# Main.net
KiCad netlist of a schematic drawn in Altium Designer
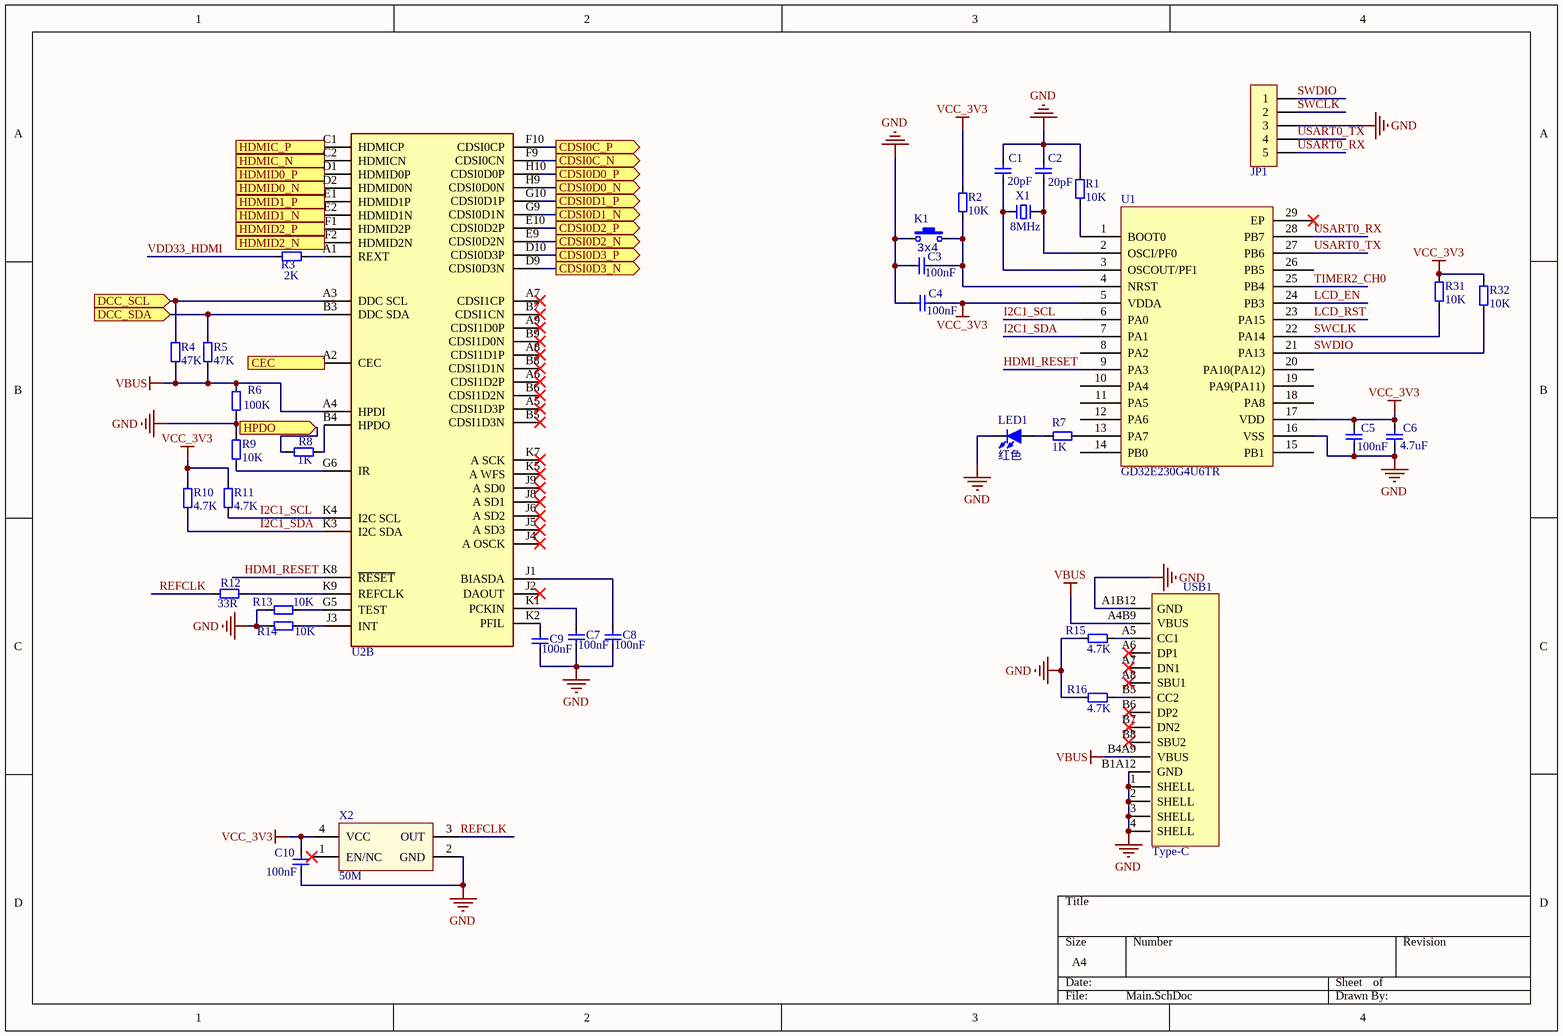
[diagram p0: Main.SchDoc]

(export (version "E")
  (design (tool "Eeschema 10.0.6"))
  (components
    (comp (ref "C1")
      (value "20pF")
      (footprint "C0402_L")
      (description "贴片电容")
      (libsource (lib "0.1 - 电阻-电容-电感-磁珠-电位器") (part "C"))
    )
    (comp (ref "C2")
      (value "20pF")
      (footprint "C0402_L")
      (description "贴片电容")
      (libsource (lib "0.1 - 电阻-电容-电感-磁珠-电位器") (part "C"))
    )
    (comp (ref "C3")
      (value "100nF")
      (footprint "C0402_L")
      (description "贴片电容")
      (libsource (lib "0.1 - 电阻-电容-电感-磁珠-电位器") (part "C"))
    )
    (comp (ref "C4")
      (value "100nF")
      (footprint "C0402_L")
      (description "贴片电容")
      (libsource (lib "0.1 - 电阻-电容-电感-磁珠-电位器") (part "C"))
    )
    (comp (ref "C5")
      (value "100nF")
      (footprint "C0402_L")
      (description "贴片电容")
      (libsource (lib "0.1 - 电阻-电容-电感-磁珠-电位器") (part "C"))
    )
    (comp (ref "C6")
      (value "4.7uF")
      (footprint "C0402_L")
      (description "贴片电容")
      (libsource (lib "0.1 - 电阻-电容-电感-磁珠-电位器") (part "C"))
    )
    (comp (ref "C7")
      (value "100nF")
      (footprint "C0402_L")
      (description "贴片电容")
      (libsource (lib "0.1 - 电阻-电容-电感-磁珠-电位器") (part "C"))
    )
    (comp (ref "C8")
      (value "100nF")
      (footprint "C0402_L")
      (description "贴片电容")
      (libsource (lib "0.1 - 电阻-电容-电感-磁珠-电位器") (part "C"))
    )
    (comp (ref "C9")
      (value "100nF")
      (footprint "C0402_L")
      (description "贴片电容")
      (libsource (lib "0.1 - 电阻-电容-电感-磁珠-电位器") (part "C"))
    )
    (comp (ref "C10")
      (value "100nF")
      (footprint "C0402_L")
      (description "贴片电容")
      (libsource (lib "0.1 - 电阻-电容-电感-磁珠-电位器") (part "C"))
    )
    (comp (ref "JP1")
      (value "HDR-1X5")
      (footprint "Test-2.54-5P")
      (description "5P接插件")
      (fields (field (name "版权归属") "源创客"))
      (libsource (lib "4.5   - 接插件-脚距2.54") (part "Header 5"))
    )
    (comp (ref "K1")
      (value "3x4")
      (footprint "ButtonTACT_3x4x2_180H")
      (description "Button")
      (libsource (lib "User") (part "ButtonTACT_3x4x2_180"))
    )
    (comp (ref "LED1")
      (value "红色")
      (footprint "LED0402")
      (description "贴片LED")
      (libsource (lib "0.3 - LED发光二极管") (part "LED-SMD"))
    )
    (comp (ref "R1")
      (value "10K")
      (footprint "R0402_L")
      (description "贴片电阻")
      (libsource (lib "0.1 - 电阻-电容-电感-磁珠-电位器") (part "R"))
    )
    (comp (ref "R2")
      (value "10K")
      (footprint "R0402_L")
      (description "贴片电阻")
      (libsource (lib "0.1 - 电阻-电容-电感-磁珠-电位器") (part "R"))
    )
    (comp (ref "R3")
      (value "2K")
      (footprint "R0402_L")
      (description "贴片电阻")
      (libsource (lib "0.1 - 电阻-电容-电感-磁珠-电位器") (part "R"))
    )
    (comp (ref "R4")
      (value "47K")
      (footprint "R0402_L")
      (description "贴片电阻")
      (libsource (lib "0.1 - 电阻-电容-电感-磁珠-电位器") (part "R"))
    )
    (comp (ref "R5")
      (value "47K")
      (footprint "R0402_L")
      (description "贴片电阻")
      (libsource (lib "0.1 - 电阻-电容-电感-磁珠-电位器") (part "R"))
    )
    (comp (ref "R6")
      (value "100K")
      (footprint "R0402_L")
      (description "贴片电阻")
      (libsource (lib "0.1 - 电阻-电容-电感-磁珠-电位器") (part "R"))
    )
    (comp (ref "R7")
      (value "1K")
      (footprint "R0402_L")
      (description "贴片电阻")
      (libsource (lib "0.1 - 电阻-电容-电感-磁珠-电位器") (part "R"))
    )
    (comp (ref "R8")
      (value "1K")
      (footprint "R0402_L")
      (description "贴片电阻")
      (libsource (lib "0.1 - 电阻-电容-电感-磁珠-电位器") (part "R"))
    )
    (comp (ref "R9")
      (value "10K")
      (footprint "R0402_L")
      (description "贴片电阻")
      (libsource (lib "0.1 - 电阻-电容-电感-磁珠-电位器") (part "R"))
    )
    (comp (ref "R10")
      (value "4.7K")
      (footprint "R0402_L")
      (description "贴片电阻")
      (libsource (lib "0.1 - 电阻-电容-电感-磁珠-电位器") (part "R"))
    )
    (comp (ref "R11")
      (value "4.7K")
      (footprint "R0402_L")
      (description "贴片电阻")
      (libsource (lib "0.1 - 电阻-电容-电感-磁珠-电位器") (part "R"))
    )
    (comp (ref "R12")
      (value "33R")
      (footprint "R0402_L")
      (description "贴片电阻")
      (libsource (lib "0.1 - 电阻-电容-电感-磁珠-电位器") (part "R"))
    )
    (comp (ref "R13")
      (value "10K")
      (footprint "R0402_L")
      (description "贴片电阻")
      (libsource (lib "0.1 - 电阻-电容-电感-磁珠-电位器") (part "R"))
    )
    (comp (ref "R14")
      (value "10K")
      (footprint "R0402_L")
      (description "贴片电阻")
      (libsource (lib "0.1 - 电阻-电容-电感-磁珠-电位器") (part "R"))
    )
    (comp (ref "R15")
      (value "4.7K")
      (footprint "R0402_L")
      (description "贴片电阻")
      (libsource (lib "0.1 - 电阻-电容-电感-磁珠-电位器") (part "R"))
    )
    (comp (ref "R16")
      (value "4.7K")
      (footprint "R0402_L")
      (description "贴片电阻")
      (libsource (lib "0.1 - 电阻-电容-电感-磁珠-电位器") (part "R"))
    )
    (comp (ref "R31")
      (value "10K")
      (footprint "R0402_L")
      (description "贴片电阻")
      (libsource (lib "0.1 - 电阻-电容-电感-磁珠-电位器") (part "R"))
    )
    (comp (ref "R32")
      (value "10K")
      (footprint "R0402_L")
      (description "贴片电阻")
      (libsource (lib "0.1 - 电阻-电容-电感-磁珠-电位器") (part "R"))
    )
    (comp (ref "U1")
      (value "GD32E230G4U6TR")
      (footprint "GD32E230G4U6TR")
      (libsource (lib "User") (part "GD32E230G4U6TR"))
    )
    (comp (ref "U2")
      (value "TC358870XBG")
      (footprint "TC358870XBG")
      (libsource (lib "User") (part "TC358870XBG"))
    )
    (comp (ref "USB1") (value "Type-C") (footprint "Type-C 16P") (libsource (lib "User") (part "Type-C")))
    (comp (ref "X1")
      (value "8MHz")
      (footprint "OSC 5032-8M")
      (description "2脚无源脚晶振")
      (libsource (lib "0.5 - 保险丝-晶振-光耦") (part "XTAL-2P"))
    )
    (comp (ref "X2")
      (value "50M")
      (footprint "OSC 3225-4P")
      (description "4脚有源晶振")
      (libsource (lib "0.5 - 保险丝-晶振-光耦") (part "XTAL-ACT-4P"))
    )
  )
  (nets
    (net (code "1") (name "/CDSI0C_N") (class "Default")
      (node (ref "U2") (pin "F9") (pinfunction "CDSI0CN_F9") (pintype "passive"))
    )
    (net (code "2") (name "/CDSI0C_P") (class "Default")
      (node (ref "U2") (pin "F10") (pinfunction "CDSI0CP_F10") (pintype "passive"))
    )
    (net (code "3") (name "/CDSI0D0_N") (class "Default")
      (node (ref "U2") (pin "H9") (pinfunction "CDSI0D0N_H9") (pintype "passive"))
    )
    (net (code "4") (name "/CDSI0D0_P") (class "Default")
      (node (ref "U2") (pin "H10") (pinfunction "CDSI0D0P_H10") (pintype "passive"))
    )
    (net (code "5") (name "/CDSI0D1_N") (class "Default")
      (node (ref "U2") (pin "G9") (pinfunction "CDSI0D1N_G9") (pintype "passive"))
    )
    (net (code "6") (name "/CDSI0D1_P") (class "Default")
      (node (ref "U2") (pin "G10") (pinfunction "CDSI0D1P_G10") (pintype "passive"))
    )
    (net (code "7") (name "/CDSI0D2_N") (class "Default")
      (node (ref "U2") (pin "E9") (pinfunction "CDSI0D2N_E9") (pintype "passive"))
    )
    (net (code "8") (name "/CDSI0D2_P") (class "Default")
      (node (ref "U2") (pin "E10") (pinfunction "CDSI0D2P_E10") (pintype "passive"))
    )
    (net (code "9") (name "/CDSI0D3_N") (class "Default")
      (node (ref "U2") (pin "D9") (pinfunction "CDSI0D3N_D9") (pintype "passive"))
    )
    (net (code "10") (name "/CDSI0D3_P") (class "Default")
      (node (ref "U2") (pin "D10") (pinfunction "CDSI0D3P_D10") (pintype "passive"))
    )
    (net (code "11") (name "/CEC") (class "Default")
      (node (ref "U2") (pin "A2") (pinfunction "CEC_A2") (pintype "passive"))
    )
    (net (code "12") (name "/DCC_SCL") (class "Default")
      (node (ref "R4") (pin "2") (pinfunction "2_2") (pintype "passive"))
      (node (ref "U2") (pin "A3") (pinfunction "DDC_SCL_A3") (pintype "passive"))
    )
    (net (code "13") (name "/DCC_SDA") (class "Default")
      (node (ref "R5") (pin "2") (pinfunction "2_2") (pintype "passive"))
      (node (ref "U2") (pin "B3") (pinfunction "DDC_SDA_B3") (pintype "passive"))
    )
    (net (code "14") (name "/HDMIC_N") (class "Default")
      (node (ref "U2") (pin "C2") (pinfunction "HDMICN_C2") (pintype "passive"))
    )
    (net (code "15") (name "/HDMIC_P") (class "Default")
      (node (ref "U2") (pin "C1") (pinfunction "HDMICP_C1") (pintype "passive"))
    )
    (net (code "16") (name "/HDMID0_N") (class "Default")
      (node (ref "U2") (pin "D2") (pinfunction "HDMID0N_D2") (pintype "passive"))
    )
    (net (code "17") (name "/HDMID0_P") (class "Default")
      (node (ref "U2") (pin "D1") (pinfunction "HDMID0P_D1") (pintype "passive"))
    )
    (net (code "18") (name "/HDMID1_N") (class "Default")
      (node (ref "U2") (pin "E2") (pinfunction "HDMID1N_E2") (pintype "passive"))
    )
    (net (code "19") (name "/HDMID1_P") (class "Default")
      (node (ref "U2") (pin "E1") (pinfunction "HDMID1P_E1") (pintype "passive"))
    )
    (net (code "20") (name "/HDMID2_N") (class "Default")
      (node (ref "U2") (pin "F2") (pinfunction "HDMID2N_F2") (pintype "passive"))
    )
    (net (code "21") (name "/HDMID2_P") (class "Default")
      (node (ref "U2") (pin "F1") (pinfunction "HDMID2P_F1") (pintype "passive"))
    )
    (net (code "22") (name "/HDMI_RESET") (class "Default")
      (node (ref "U1") (pin "9") (pinfunction "PA3_9") (pintype "passive"))
      (node (ref "U2") (pin "K8") (pinfunction "~{RESET}_K8") (pintype "passive"))
    )
    (net (code "23") (name "/HPDO") (class "Default")
      (node (ref "R8") (pin "2") (pinfunction "2_2") (pintype "passive"))
    )
    (net (code "24") (name "/I2C1_SCL") (class "Default")
      (node (ref "R11") (pin "2") (pinfunction "2_2") (pintype "passive"))
      (node (ref "U1") (pin "6") (pinfunction "PA0_6") (pintype "passive"))
      (node (ref "U2") (pin "K4") (pinfunction "I2C_SCL_K4") (pintype "passive"))
    )
    (net (code "25") (name "/I2C1_SDA") (class "Default")
      (node (ref "R10") (pin "2") (pinfunction "2_2") (pintype "passive"))
      (node (ref "U1") (pin "7") (pinfunction "PA1_7") (pintype "passive"))
      (node (ref "U2") (pin "K3") (pinfunction "I2C_SDA_K3") (pintype "passive"))
    )
    (net (code "26") (name "/LCD_EN") (class "Default")
      (node (ref "U1") (pin "24") (pinfunction "PB3_24") (pintype "passive"))
    )
    (net (code "27") (name "/LCD_RST") (class "Default")
      (node (ref "U1") (pin "23") (pinfunction "PA15_23") (pintype "passive"))
    )
    (net (code "28") (name "/REFCLK") (class "Default")
      (node (ref "R12") (pin "2") (pinfunction "2_2") (pintype "passive"))
      (node (ref "X2") (pin "3") (pinfunction "OUT_3") (pintype "passive"))
    )
    (net (code "29") (name "/SWCLK") (class "Default")
      (node (ref "JP1") (pin "2") (pinfunction "2_2") (pintype "passive"))
      (node (ref "R31") (pin "2") (pinfunction "2_2") (pintype "passive"))
      (node (ref "U1") (pin "22") (pinfunction "PA14_22") (pintype "passive"))
    )
    (net (code "30") (name "/SWDIO") (class "Default")
      (node (ref "JP1") (pin "1") (pinfunction "1_1") (pintype "passive"))
      (node (ref "R32") (pin "2") (pinfunction "2_2") (pintype "passive"))
      (node (ref "U1") (pin "21") (pinfunction "PA13_21") (pintype "passive"))
    )
    (net (code "31") (name "/TIMER2_CH0") (class "Default")
      (node (ref "U1") (pin "25") (pinfunction "PB4_25") (pintype "passive"))
    )
    (net (code "32") (name "/USART0_RX") (class "Default")
      (node (ref "JP1") (pin "5") (pinfunction "5_5") (pintype "passive"))
      (node (ref "U1") (pin "28") (pinfunction "PB7_28") (pintype "passive"))
    )
    (net (code "33") (name "/USART0_TX") (class "Default")
      (node (ref "JP1") (pin "4") (pinfunction "4_4") (pintype "passive"))
      (node (ref "U1") (pin "27") (pinfunction "PB6_27") (pintype "passive"))
    )
    (net (code "34") (name "/VDD33_HDMI") (class "Default")
      (node (ref "R3") (pin "2") (pinfunction "2_2") (pintype "passive"))
    )
    (net (code "35") (name "GND") (class "Default")
      (node (ref "C1") (pin "2") (pinfunction "2_2") (pintype "passive"))
      (node (ref "C10") (pin "1") (pinfunction "1_1") (pintype "passive"))
      (node (ref "C2") (pin "2") (pinfunction "2_2") (pintype "passive"))
      (node (ref "C3") (pin "2") (pinfunction "2_2") (pintype "passive"))
      (node (ref "C4") (pin "2") (pinfunction "2_2") (pintype "passive"))
      (node (ref "C5") (pin "2") (pinfunction "2_2") (pintype "passive"))
      (node (ref "C6") (pin "2") (pinfunction "2_2") (pintype "passive"))
      (node (ref "C7") (pin "2") (pinfunction "2_2") (pintype "passive"))
      (node (ref "C8") (pin "1") (pinfunction "1_1") (pintype "passive"))
      (node (ref "C9") (pin "1") (pinfunction "1_1") (pintype "passive"))
      (node (ref "JP1") (pin "3") (pinfunction "3_3") (pintype "passive"))
      (node (ref "K1") (pin "1") (pinfunction "1_1") (pintype "passive"))
      (node (ref "LED1") (pin "2") (pinfunction "K_2") (pintype "passive"))
      (node (ref "R1") (pin "1") (pinfunction "1_1") (pintype "passive"))
      (node (ref "R13") (pin "2") (pinfunction "2_2") (pintype "passive"))
      (node (ref "R14") (pin "2") (pinfunction "2_2") (pintype "passive"))
      (node (ref "R15") (pin "2") (pinfunction "2_2") (pintype "passive"))
      (node (ref "R16") (pin "2") (pinfunction "2_2") (pintype "passive"))
      (node (ref "R6") (pin "2") (pinfunction "2_2") (pintype "passive"))
      (node (ref "R9") (pin "2") (pinfunction "2_2") (pintype "passive"))
      (node (ref "U1") (pin "16") (pinfunction "VSS_16") (pintype "passive"))
      (node (ref "USB1") (pin "1") (pinfunction "SHELL_1") (pintype "passive"))
      (node (ref "USB1") (pin "2") (pinfunction "SHELL_2") (pintype "passive"))
      (node (ref "USB1") (pin "3") (pinfunction "SHELL_3") (pintype "passive"))
      (node (ref "USB1") (pin "4") (pinfunction "SHELL_4") (pintype "passive"))
      (node (ref "USB1") (pin "A1B12") (pinfunction "GND_A1B12") (pintype "passive"))
      (node (ref "USB1") (pin "B1A12") (pinfunction "GND_B1A12") (pintype "passive"))
      (node (ref "X2") (pin "2") (pinfunction "GND_2") (pintype "passive"))
    )
    (net (code "36") (name "Net-(LED1-A)") (class "Default")
      (node (ref "LED1") (pin "1") (pinfunction "A_1") (pintype "passive"))
      (node (ref "R7") (pin "1") (pinfunction "1_1") (pintype "passive"))
    )
    (net (code "37") (name "Net-(U1-BOOT0)") (class "Default")
      (node (ref "R1") (pin "2") (pinfunction "2_2") (pintype "passive"))
      (node (ref "U1") (pin "1") (pinfunction "BOOT0_1") (pintype "passive"))
    )
    (net (code "38") (name "Net-(U1-NRST)") (class "Default")
      (node (ref "C3") (pin "1") (pinfunction "1_1") (pintype "passive"))
      (node (ref "K1") (pin "2") (pinfunction "2_2") (pintype "passive"))
      (node (ref "R2") (pin "2") (pinfunction "2_2") (pintype "passive"))
      (node (ref "U1") (pin "4") (pinfunction "NRST_4") (pintype "passive"))
    )
    (net (code "39") (name "Net-(U1-OSCI{slash}PF0)") (class "Default")
      (node (ref "C2") (pin "1") (pinfunction "1_1") (pintype "passive"))
      (node (ref "U1") (pin "2") (pinfunction "OSCI/PF0_2") (pintype "passive"))
      (node (ref "X1") (pin "2") (pinfunction "2_2") (pintype "passive"))
    )
    (net (code "40") (name "Net-(U1-OSCOUT{slash}PF1)") (class "Default")
      (node (ref "C1") (pin "1") (pinfunction "1_1") (pintype "passive"))
      (node (ref "U1") (pin "3") (pinfunction "OSCOUT/PF1_3") (pintype "passive"))
      (node (ref "X1") (pin "1") (pinfunction "1_1") (pintype "passive"))
    )
    (net (code "41") (name "Net-(U1-PA7)") (class "Default")
      (node (ref "R7") (pin "2") (pinfunction "2_2") (pintype "passive"))
      (node (ref "U1") (pin "13") (pinfunction "PA7_13") (pintype "passive"))
    )
    (net (code "42") (name "Net-(U2B-BIASDA)") (class "Default")
      (node (ref "C8") (pin "2") (pinfunction "2_2") (pintype "passive"))
      (node (ref "U2") (pin "J1") (pinfunction "BIASDA_J1") (pintype "passive"))
    )
    (net (code "43") (name "Net-(U2B-HPDO)") (class "Default")
      (node (ref "R8") (pin "1") (pinfunction "1_1") (pintype "passive"))
      (node (ref "U2") (pin "B4") (pinfunction "HPDO_B4") (pintype "passive"))
    )
    (net (code "44") (name "Net-(U2B-INT)") (class "Default")
      (node (ref "R14") (pin "1") (pinfunction "1_1") (pintype "passive"))
      (node (ref "U2") (pin "J3") (pinfunction "INT_J3") (pintype "passive"))
    )
    (net (code "45") (name "Net-(U2B-IR)") (class "Default")
      (node (ref "R9") (pin "1") (pinfunction "1_1") (pintype "passive"))
      (node (ref "U2") (pin "G6") (pinfunction "IR_G6") (pintype "passive"))
    )
    (net (code "46") (name "Net-(U2B-PCKIN)") (class "Default")
      (node (ref "C7") (pin "1") (pinfunction "1_1") (pintype "passive"))
      (node (ref "U2") (pin "K1") (pinfunction "PCKIN_K1") (pintype "passive"))
    )
    (net (code "47") (name "Net-(U2B-PFIL)") (class "Default")
      (node (ref "C9") (pin "2") (pinfunction "2_2") (pintype "passive"))
      (node (ref "U2") (pin "K2") (pinfunction "PFIL_K2") (pintype "passive"))
    )
    (net (code "48") (name "Net-(U2B-REFCLK)") (class "Default")
      (node (ref "R12") (pin "1") (pinfunction "1_1") (pintype "passive"))
      (node (ref "U2") (pin "K9") (pinfunction "REFCLK_K9") (pintype "passive"))
    )
    (net (code "49") (name "Net-(U2B-REXT)") (class "Default")
      (node (ref "R3") (pin "1") (pinfunction "1_1") (pintype "passive"))
      (node (ref "U2") (pin "A1") (pinfunction "REXT_A1") (pintype "passive"))
    )
    (net (code "50") (name "Net-(U2B-TEST)") (class "Default")
      (node (ref "R13") (pin "1") (pinfunction "1_1") (pintype "passive"))
      (node (ref "U2") (pin "G5") (pinfunction "TEST_G5") (pintype "passive"))
    )
    (net (code "51") (name "Net-(USB1-CC1)") (class "Default")
      (node (ref "R15") (pin "1") (pinfunction "1_1") (pintype "passive"))
      (node (ref "USB1") (pin "A5") (pinfunction "CC1_A5") (pintype "passive"))
    )
    (net (code "52") (name "Net-(USB1-CC2)") (class "Default")
      (node (ref "R16") (pin "1") (pinfunction "1_1") (pintype "passive"))
      (node (ref "USB1") (pin "B5") (pinfunction "CC2_B5") (pintype "passive"))
    )
    (net (code "53") (name "VBUS") (class "Default")
      (node (ref "R4") (pin "1") (pinfunction "1_1") (pintype "passive"))
      (node (ref "R5") (pin "1") (pinfunction "1_1") (pintype "passive"))
      (node (ref "R6") (pin "1") (pinfunction "1_1") (pintype "passive"))
      (node (ref "U2") (pin "A4") (pinfunction "HPDI_A4") (pintype "passive"))
      (node (ref "USB1") (pin "A4B9") (pinfunction "VBUS_A4B9") (pintype "passive"))
      (node (ref "USB1") (pin "B4A9") (pinfunction "VBUS_B4A9") (pintype "passive"))
    )
    (net (code "54") (name "VCC_3V3") (class "Default")
      (node (ref "C10") (pin "2") (pinfunction "2_2") (pintype "passive"))
      (node (ref "C4") (pin "1") (pinfunction "1_1") (pintype "passive"))
      (node (ref "C5") (pin "1") (pinfunction "1_1") (pintype "passive"))
      (node (ref "C6") (pin "1") (pinfunction "1_1") (pintype "passive"))
      (node (ref "R10") (pin "1") (pinfunction "1_1") (pintype "passive"))
      (node (ref "R11") (pin "1") (pinfunction "1_1") (pintype "passive"))
      (node (ref "R2") (pin "1") (pinfunction "1_1") (pintype "passive"))
      (node (ref "R31") (pin "1") (pinfunction "1_1") (pintype "passive"))
      (node (ref "R32") (pin "1") (pinfunction "1_1") (pintype "passive"))
      (node (ref "U1") (pin "17") (pinfunction "VDD_17") (pintype "passive"))
      (node (ref "U1") (pin "5") (pinfunction "VDDA_5") (pintype "passive"))
      (node (ref "X2") (pin "4") (pinfunction "VCC_4") (pintype "passive"))
    )
    (net (code "55") (name "unconnected-(U1-EP-Pad29)") (class "Default")
      (node (ref "U1") (pin "29") (pinfunction "EP_29") (pintype "passive+no_connect"))
    )
    (net (code "56") (name "unconnected-(U1-PA2-Pad8)") (class "Default")
      (node (ref "U1") (pin "8") (pinfunction "PA2_8") (pintype "passive"))
    )
    (net (code "57") (name "unconnected-(U1-PA4-Pad10)") (class "Default")
      (node (ref "U1") (pin "10") (pinfunction "PA4_10") (pintype "passive"))
    )
    (net (code "58") (name "unconnected-(U1-PA5-Pad11)") (class "Default")
      (node (ref "U1") (pin "11") (pinfunction "PA5_11") (pintype "passive"))
    )
    (net (code "59") (name "unconnected-(U1-PA6-Pad12)") (class "Default")
      (node (ref "U1") (pin "12") (pinfunction "PA6_12") (pintype "passive"))
    )
    (net (code "60") (name "unconnected-(U1-PA8-Pad18)") (class "Default")
      (node (ref "U1") (pin "18") (pinfunction "PA8_18") (pintype "passive"))
    )
    (net (code "61") (name "unconnected-(U1-PA9(PA11)-Pad19)") (class "Default")
      (node (ref "U1") (pin "19") (pinfunction "PA9(PA11)_19") (pintype "passive"))
    )
    (net (code "62") (name "unconnected-(U1-PA10(PA12)-Pad20)") (class "Default")
      (node (ref "U1") (pin "20") (pinfunction "PA10(PA12)_20") (pintype "passive"))
    )
    (net (code "63") (name "unconnected-(U1-PB0-Pad14)") (class "Default")
      (node (ref "U1") (pin "14") (pinfunction "PB0_14") (pintype "passive"))
    )
    (net (code "64") (name "unconnected-(U1-PB1-Pad15)") (class "Default")
      (node (ref "U1") (pin "15") (pinfunction "PB1_15") (pintype "passive"))
    )
    (net (code "65") (name "unconnected-(U1-PB5-Pad26)") (class "Default")
      (node (ref "U1") (pin "26") (pinfunction "PB5_26") (pintype "passive"))
    )
    (net (code "66") (name "unconnected-(U2B-A_OSCK-PadJ4)") (class "Default")
      (node (ref "U2") (pin "J4") (pinfunction "A_OSCK_J4") (pintype "passive+no_connect"))
    )
    (net (code "67") (name "unconnected-(U2B-A_SCK-PadK7)") (class "Default")
      (node (ref "U2") (pin "K7") (pinfunction "A_SCK_K7") (pintype "passive+no_connect"))
    )
    (net (code "68") (name "unconnected-(U2B-A_SD0-PadJ9)") (class "Default")
      (node (ref "U2") (pin "J9") (pinfunction "A_SD0_J9") (pintype "passive+no_connect"))
    )
    (net (code "69") (name "unconnected-(U2B-A_SD1-PadJ8)") (class "Default")
      (node (ref "U2") (pin "J8") (pinfunction "A_SD1_J8") (pintype "passive+no_connect"))
    )
    (net (code "70") (name "unconnected-(U2B-A_SD2-PadJ6)") (class "Default")
      (node (ref "U2") (pin "J6") (pinfunction "A_SD2_J6") (pintype "passive+no_connect"))
    )
    (net (code "71") (name "unconnected-(U2B-A_SD3-PadJ5)") (class "Default")
      (node (ref "U2") (pin "J5") (pinfunction "A_SD3_J5") (pintype "passive+no_connect"))
    )
    (net (code "72") (name "unconnected-(U2B-A_WFS-PadK5)") (class "Default")
      (node (ref "U2") (pin "K5") (pinfunction "A_WFS_K5") (pintype "passive+no_connect"))
    )
    (net (code "73") (name "unconnected-(U2B-CDSI1CN-PadB7)") (class "Default")
      (node (ref "U2") (pin "B7") (pinfunction "CDSI1CN_B7") (pintype "passive+no_connect"))
    )
    (net (code "74") (name "unconnected-(U2B-CDSI1CP-PadA7)") (class "Default")
      (node (ref "U2") (pin "A7") (pinfunction "CDSI1CP_A7") (pintype "passive+no_connect"))
    )
    (net (code "75") (name "unconnected-(U2B-CDSI1D0N-PadB9)") (class "Default")
      (node (ref "U2") (pin "B9") (pinfunction "CDSI1D0N_B9") (pintype "passive+no_connect"))
    )
    (net (code "76") (name "unconnected-(U2B-CDSI1D0P-PadA9)") (class "Default")
      (node (ref "U2") (pin "A9") (pinfunction "CDSI1D0P_A9") (pintype "passive+no_connect"))
    )
    (net (code "77") (name "unconnected-(U2B-CDSI1D1N-PadB8)") (class "Default")
      (node (ref "U2") (pin "B8") (pinfunction "CDSI1D1N_B8") (pintype "passive+no_connect"))
    )
    (net (code "78") (name "unconnected-(U2B-CDSI1D1P-PadA8)") (class "Default")
      (node (ref "U2") (pin "A8") (pinfunction "CDSI1D1P_A8") (pintype "passive+no_connect"))
    )
    (net (code "79") (name "unconnected-(U2B-CDSI1D2N-PadB6)") (class "Default")
      (node (ref "U2") (pin "B6") (pinfunction "CDSI1D2N_B6") (pintype "passive+no_connect"))
    )
    (net (code "80") (name "unconnected-(U2B-CDSI1D2P-PadA6)") (class "Default")
      (node (ref "U2") (pin "A6") (pinfunction "CDSI1D2P_A6") (pintype "passive+no_connect"))
    )
    (net (code "81") (name "unconnected-(U2B-CDSI1D3N-PadB5)") (class "Default")
      (node (ref "U2") (pin "B5") (pinfunction "CDSI1D3N_B5") (pintype "passive+no_connect"))
    )
    (net (code "82") (name "unconnected-(U2B-CDSI1D3P-PadA5)") (class "Default")
      (node (ref "U2") (pin "A5") (pinfunction "CDSI1D3P_A5") (pintype "passive+no_connect"))
    )
    (net (code "83") (name "unconnected-(U2B-DAOUT-PadJ2)") (class "Default")
      (node (ref "U2") (pin "J2") (pinfunction "DAOUT_J2") (pintype "passive+no_connect"))
    )
    (net (code "84") (name "unconnected-(USB1-DN1-PadA7)") (class "Default")
      (node (ref "USB1") (pin "A7") (pinfunction "DN1_A7") (pintype "passive+no_connect"))
    )
    (net (code "85") (name "unconnected-(USB1-DN2-PadB7)") (class "Default")
      (node (ref "USB1") (pin "B7") (pinfunction "DN2_B7") (pintype "passive+no_connect"))
    )
    (net (code "86") (name "unconnected-(USB1-DP1-PadA6)") (class "Default")
      (node (ref "USB1") (pin "A6") (pinfunction "DP1_A6") (pintype "passive+no_connect"))
    )
    (net (code "87") (name "unconnected-(USB1-DP2-PadB6)") (class "Default")
      (node (ref "USB1") (pin "B6") (pinfunction "DP2_B6") (pintype "passive+no_connect"))
    )
    (net (code "88") (name "unconnected-(USB1-SBU1-PadA8)") (class "Default")
      (node (ref "USB1") (pin "A8") (pinfunction "SBU1_A8") (pintype "passive+no_connect"))
    )
    (net (code "89") (name "unconnected-(USB1-SBU2-PadB8)") (class "Default")
      (node (ref "USB1") (pin "B8") (pinfunction "SBU2_B8") (pintype "passive+no_connect"))
    )
    (net (code "90") (name "unconnected-(X2-EN{slash}NC-Pad1)") (class "Default")
      (node (ref "X2") (pin "1") (pinfunction "EN/NC_1") (pintype "passive+no_connect"))
    )
  )
)
